# Rat_Social_Box_Extension.net
KiCad netlist of a schematic drawn in Altium Designer
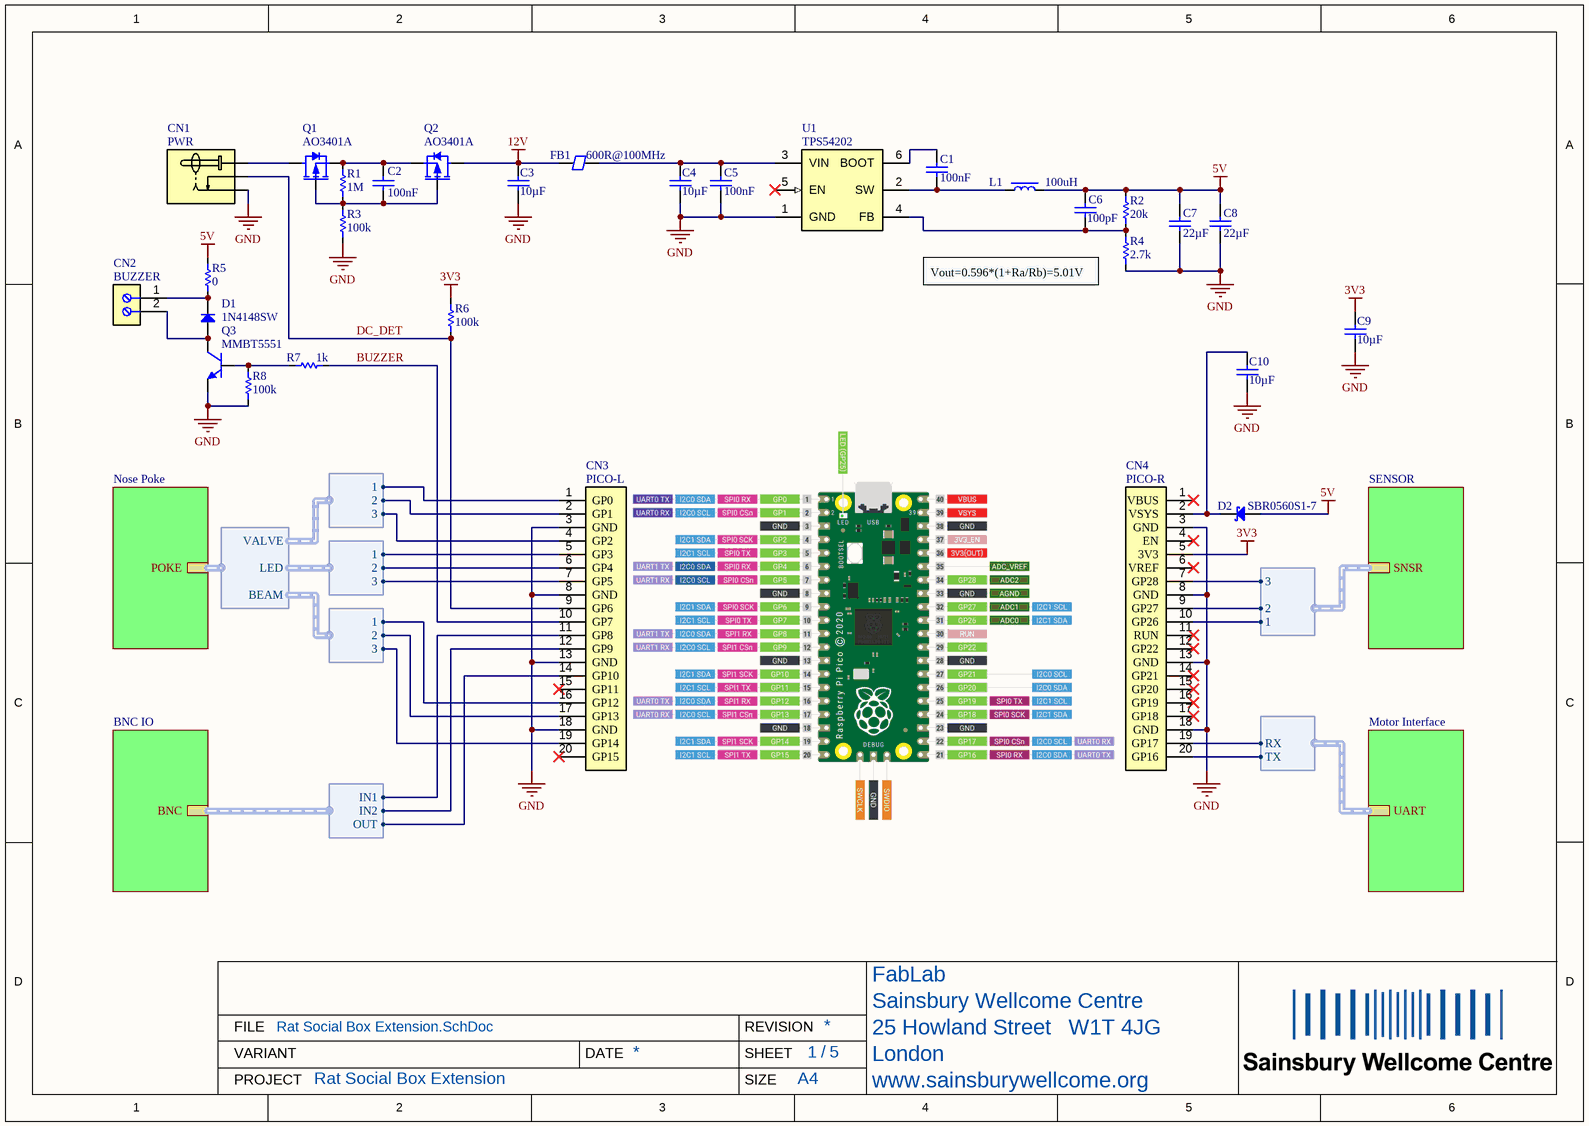
[diagram p0: Rat Social Box Extension.SchDoc]

(export (version "E")
  (design (tool "Eeschema 10.0.6"))
  (components
    (comp (ref "C1")
      (value "100nF")
      (footprint "CAP_CHIP_0603")
      (description "0603 Multilayer Ceramic Capacitors MLCC")
      (fields (field (name "TOLERANCE") "10%") (field (name "PARTNUMBER") "CC0603KRX7R9BB104"))
      (libsource (lib "Sainsbury Wellcome Centre") (part "Cap"))
    )
    (comp (ref "C2")
      (value "100nF")
      (footprint "CAP_CHIP_0603")
      (description "0603 Multilayer Ceramic Capacitors MLCC")
      (fields (field (name "PARTNUMBER") "CC0603KRX7R9BB104") (field (name "TOLERANCE") "10%"))
      (libsource (lib "Sainsbury Wellcome Centre") (part "Cap"))
    )
    (comp (ref "C3")
      (value "10µF")
      (footprint "CAP_CHIP_0603")
      (description "0603 Multilayer Ceramic Capacitors MLCC")
      (fields (field (name "PARTNUMBER") "CL10A106MA8NRNC") (field (name "TOLERANCE") "20%"))
      (libsource (lib "Sainsbury Wellcome Centre") (part "Cap"))
    )
    (comp (ref "C4")
      (value "10µF")
      (footprint "CAP_CHIP_0603")
      (description "0603 Multilayer Ceramic Capacitors MLCC")
      (fields (field (name "PARTNUMBER") "CL10A106MA8NRNC") (field (name "TOLERANCE") "20%"))
      (libsource (lib "Sainsbury Wellcome Centre") (part "Cap"))
    )
    (comp (ref "C5")
      (value "100nF")
      (footprint "CAP_CHIP_0603")
      (description "0603 Multilayer Ceramic Capacitors MLCC")
      (fields (field (name "TOLERANCE") "10%") (field (name "PARTNUMBER") "CC0603KRX7R9BB104"))
      (libsource (lib "Sainsbury Wellcome Centre") (part "Cap"))
    )
    (comp (ref "C6")
      (value "100pF")
      (footprint "CAP_CHIP_0603")
      (description "0603 Multilayer Ceramic Capacitors MLCC")
      (fields (field (name "TOLERANCE") "5%") (field (name "PARTNUMBER") "CL10C101JB8NNNC"))
      (libsource (lib "Sainsbury Wellcome Centre") (part "Cap"))
    )
    (comp (ref "C7")
      (value "22µF")
      (footprint "CAP_CHIP_0603")
      (description "0603 Multilayer Ceramic Capacitors MLCC")
      (fields (field (name "PARTNUMBER") "CL10A226MQ8NRNC") (field (name "TOLERANCE") "20%"))
      (libsource (lib "Sainsbury Wellcome Centre") (part "Cap"))
    )
    (comp (ref "C8")
      (value "22µF")
      (footprint "CAP_CHIP_0603")
      (description "0603 Multilayer Ceramic Capacitors MLCC")
      (fields (field (name "PARTNUMBER") "CL10A226MQ8NRNC") (field (name "TOLERANCE") "20%"))
      (libsource (lib "Sainsbury Wellcome Centre") (part "Cap"))
    )
    (comp (ref "C9")
      (value "10µF")
      (footprint "CAP_CHIP_0603")
      (description "0603 Multilayer Ceramic Capacitors MLCC")
      (fields (field (name "PARTNUMBER") "CL10A106MA8NRNC") (field (name "TOLERANCE") "20%"))
      (libsource (lib "Sainsbury Wellcome Centre") (part "Cap"))
    )
    (comp (ref "C10")
      (value "10µF")
      (footprint "CAP_CHIP_0603")
      (description "0603 Multilayer Ceramic Capacitors MLCC")
      (fields (field (name "PARTNUMBER") "CL10A106MA8NRNC") (field (name "TOLERANCE") "20%"))
      (libsource (lib "Sainsbury Wellcome Centre") (part "Cap"))
    )
    (comp (ref "CN1")
      (value "PWR")
      (footprint "DC-005-2.0")
      (description "Surface Mount, Right Angle 2.5A 24V SMD DC Power Connector")
      (fields (field (name "PARTNUMBER") "DC-005-2.5A-2.0-SMT"))
      (libsource (lib "Sainsbury Wellcome Centre") (part "DC Power Jack"))
    )
    (comp (ref "CN2")
      (value "BUZZER")
      (footprint "TH-5.00-1X2P")
      (description "1x2P 20A -40℃~+105℃ 250V Green 12~22 Direct Insert 5mm 2.5 1 2 Plugin,P=5mm Screw Terminal Blocks")
      (fields (field (name "PARTNUMBER") "WJ128V-5.0-2P"))
      (libsource (lib "Sainsbury Wellcome Centre") (part "Terminal Block 2"))
    )
    (comp (ref "CN3")
      (value "PICO-L")
      (footprint "FM_2.54_1X20P")
      (description "8.5mm Square Hole TH,P=2.54mm Female Headers")
      (fields (field (name "PARTNUMBER") "22850120ANG1SYA01"))
      (libsource (lib "Sainsbury Wellcome Centre") (part "Header_1X20P"))
    )
    (comp (ref "CN4")
      (value "PICO-R")
      (footprint "FM_2.54_1X20P")
      (description "8.5mm Square Hole TH,P=2.54mm Female Headers")
      (fields (field (name "PARTNUMBER") "22850120ANG1SYA01"))
      (libsource (lib "") (part "Header_1X20P_1"))
    )
    (comp (ref "D1")
      (value "1N4148SW")
      (footprint "SOD323")
      (description "100V Single 1.25V@150mA 4ns 150mA SOD-323 Switching Diode")
      (libsource (lib "Sainsbury Wellcome Centre") (part "Diode 2P"))
    )
    (comp (ref "D2")
      (value "SBR0560S1-7")
      (footprint "SOD123")
      (description "Diode Schottky 60V 0.5A 2-Pin SOD-123 T/R")
      (libsource (lib "Sainsbury Wellcome Centre") (part "Diode-Schottky"))
    )
    (comp (ref "FB1")
      (value "600R@100MHz")
      (footprint "FB_CHIP_0805")
      (description "Ferrite Chip, 1 Function(s), 0.5A, 2 Pin(s)")
      (fields (field (name "PARTNUMBER") "GZ2012D601TF") (field (name "Comment") "FB0805-600R-0.5A"))
      (libsource (lib "Sainsbury Wellcome Centre") (part "Bead"))
    )
    (comp (ref "L1")
      (value "100uH")
      (footprint "IND_PWR_0402L")
      (description "Inductor Power Shielded Wirewound 100uH 20% 100KHz Ferrite 450mA DCR 1515 Blister T/R")
      (fields (field (name "PARTNUMBER") "VLCF4020T-101MR26") (field (name "TOLERANCE") "20%"))
      (libsource (lib "Sainsbury Wellcome Centre") (part "Inductor"))
    )
    (comp (ref "Q1")
      (value "AO3401A")
      (footprint "SOT23")
      (description "30V 4A 44mΩ@10V,4.3A 1.4W 1.3V@250uA 1 PChannel SOT-23-3L MOSFETs")
      (fields (field (name "PARTNUMBER") "AO3401A"))
      (libsource (lib "Sainsbury Wellcome Centre") (part "PMOS"))
    )
    (comp (ref "Q2")
      (value "AO3401A")
      (footprint "SOT23")
      (description "30V 4A 44mΩ@10V,4.3A 1.4W 1.3V@250uA 1 PChannel SOT-23-3L MOSFETs")
      (fields (field (name "PARTNUMBER") "AO3401A"))
      (libsource (lib "Sainsbury Wellcome Centre") (part "PMOS"))
    )
    (comp (ref "Q3")
      (value "MMBT5551")
      (footprint "SOT23")
      (description "160V 300mW 200@10mA 5V 600mA NPN SOT-23 Bipolar Transistor")
      (fields (field (name "PARTNUMBER") "MMBT5551"))
      (libsource (lib "Sainsbury Wellcome Centre") (part "BJT NPN"))
    )
    (comp (ref "R1")
      (value "1M")
      (footprint "RES_CHIP_0603")
      (description "100mW Thick Film Resistors 75V ±100ppm/℃ ±1% 0603 Chip Resistor")
      (fields (field (name "PARTNUMBER") "0603WAF1004T5E") (field (name "TOLERANCE") "1%"))
      (libsource (lib "Sainsbury Wellcome Centre") (part "Res"))
    )
    (comp (ref "R2")
      (value "20k")
      (footprint "RES_CHIP_0603")
      (description "100mW Thick Film Resistors 75V ±100ppm/℃ ±1% 0603 Chip Resistor")
      (fields (field (name "TOLERANCE") "1%") (field (name "PARTNUMBER") "0603WAF2002T5E"))
      (libsource (lib "Sainsbury Wellcome Centre") (part "Res"))
    )
    (comp (ref "R3")
      (value "100k")
      (footprint "RES_CHIP_0603")
      (description "100mW Thick Film Resistors 75V ±100ppm/℃ ±1% 0603 Chip Resistor")
      (fields (field (name "PARTNUMBER") "0603WAF1003T5E") (field (name "TOLERANCE") "1%"))
      (libsource (lib "Sainsbury Wellcome Centre") (part "Res"))
    )
    (comp (ref "R4")
      (value "2.7k")
      (footprint "RES_CHIP_0603")
      (description "100mW Thick Film Resistors 75V ±100ppm/℃ ±1% 0603 Chip Resistor")
      (fields (field (name "TOLERANCE") "1%") (field (name "PARTNUMBER") "0603WAF2701T5E"))
      (libsource (lib "Sainsbury Wellcome Centre") (part "Res"))
    )
    (comp (ref "R5")
      (value "0")
      (footprint "RES_CHIP_1206")
      (description "250mW Thick Film Resistors 200V ±800ppm/℃ ±1% 0Ω 1206 Chip Resistor")
      (fields (field (name "TOLERANCE") "1%") (field (name "PARTNUMBER") "1206W4F0000T5E"))
      (libsource (lib "Sainsbury Wellcome Centre") (part "Res"))
    )
    (comp (ref "R6")
      (value "100k")
      (footprint "RES_CHIP_0603")
      (description "100mW Thick Film Resistors 75V ±100ppm/℃ ±1% 0603 Chip Resistor")
      (fields (field (name "PARTNUMBER") "0603WAF1003T5E") (field (name "TOLERANCE") "1%"))
      (libsource (lib "Sainsbury Wellcome Centre") (part "Res"))
    )
    (comp (ref "R7")
      (value "1k")
      (footprint "RES_CHIP_0603")
      (description "100mW Thick Film Resistors 75V ±100ppm/℃ ±1% 0603 Chip Resistor")
      (fields (field (name "PARTNUMBER") "0603WAF1001T5E") (field (name "TOLERANCE") "1%"))
      (libsource (lib "Sainsbury Wellcome Centre") (part "Res"))
    )
    (comp (ref "R8")
      (value "100k")
      (footprint "RES_CHIP_0603")
      (description "100mW Thick Film Resistors 75V ±100ppm/℃ ±1% 0603 Chip Resistor")
      (fields (field (name "PARTNUMBER") "0603WAF1003T5E") (field (name "TOLERANCE") "1%"))
      (libsource (lib "Sainsbury Wellcome Centre") (part "Res"))
    )
    (comp (ref "U1")
      (value "TPS54202")
      (footprint "SOT23-6")
      (description "Switching Regulator, Current-mode, 2A, 500kHz Switching Freq-Max, PDSO6")
      (fields (field (name "PARTNUMBER") "TPS54202DDCR"))
      (libsource (lib "Sainsbury Wellcome Centre") (part "TPS54202"))
    )
  )
  (nets
    (net (code "7") (name "/BUZZER") (class "Default")
      (node (ref "CN3") (pin "10") (pinfunction "GP7_10") (pintype "passive"))
      (node (ref "R7") (pin "2") (pinfunction "2_2") (pintype "passive"))
    )
    (net (code "8") (name "/DC_DET") (class "Default")
      (node (ref "CN1") (pin "3") (pinfunction "Detect_3") (pintype "passive"))
      (node (ref "CN3") (pin "9") (pinfunction "GP6_9") (pintype "passive"))
      (node (ref "R6") (pin "1") (pinfunction "1_1") (pintype "passive"))
    )
    (net (code "9") (name "/IN1") (class "Default")
      (node (ref "CN3") (pin "11") (pinfunction "GP8_11") (pintype "passive"))
    )
    (net (code "10") (name "/IN2") (class "Default")
      (node (ref "CN3") (pin "12") (pinfunction "GP9_12") (pintype "passive"))
    )
    (net (code "11") (name "/OUT") (class "Default")
      (node (ref "CN3") (pin "14") (pinfunction "GP10_14") (pintype "passive"))
    )
    (net (code "13") (name "/RX") (class "Default")
      (node (ref "CN4") (pin "19") (pinfunction "GP17_19") (pintype "passive"))
    )
    (net (code "14") (name "/TX") (class "Default")
      (node (ref "CN4") (pin "20") (pinfunction "GP16_20") (pintype "passive"))
    )
    (net (code "21") (name "3V3") (class "Default")
      (node (ref "C9") (pin "2") (pinfunction "2_2") (pintype "passive"))
      (node (ref "CN4") (pin "5") (pinfunction "3V3_5") (pintype "passive"))
      (node (ref "R6") (pin "2") (pinfunction "2_2") (pintype "passive"))
    )
    (net (code "22") (name "5V") (class "Default")
      (node (ref "C6") (pin "2") (pinfunction "2_2") (pintype "passive"))
      (node (ref "C7") (pin "2") (pinfunction "2_2") (pintype "passive"))
      (node (ref "C8") (pin "2") (pinfunction "2_2") (pintype "passive"))
      (node (ref "D2") (pin "2") (pinfunction "A_2") (pintype "passive"))
      (node (ref "L1") (pin "2") (pinfunction "2_2") (pintype "passive"))
      (node (ref "R2") (pin "2") (pinfunction "2_2") (pintype "passive"))
      (node (ref "R5") (pin "2") (pinfunction "2_2") (pintype "passive"))
    )
    (net (code "23") (name "12V") (class "Default")
      (node (ref "C3") (pin "2") (pinfunction "2_2") (pintype "passive"))
      (node (ref "FB1") (pin "1") (pinfunction "1_1") (pintype "passive"))
      (node (ref "Q2") (pin "3") (pinfunction "D_3") (pintype "passive"))
    )
    (net (code "24") (name "GND") (class "Default")
      (node (ref "C10") (pin "1") (pinfunction "1_1") (pintype "passive"))
      (node (ref "C3") (pin "1") (pinfunction "1_1") (pintype "passive"))
      (node (ref "C4") (pin "1") (pinfunction "1_1") (pintype "passive"))
      (node (ref "C5") (pin "1") (pinfunction "1_1") (pintype "passive"))
      (node (ref "C7") (pin "1") (pinfunction "1_1") (pintype "passive"))
      (node (ref "C8") (pin "1") (pinfunction "1_1") (pintype "passive"))
      (node (ref "C9") (pin "1") (pinfunction "1_1") (pintype "passive"))
      (node (ref "CN1") (pin "2") (pinfunction "Ring_2") (pintype "passive"))
      (node (ref "CN3") (pin "13") (pinfunction "GND_13") (pintype "passive"))
      (node (ref "CN3") (pin "18") (pinfunction "GND_18") (pintype "passive"))
      (node (ref "CN3") (pin "3") (pinfunction "GND_3") (pintype "passive"))
      (node (ref "CN3") (pin "8") (pinfunction "GND_8") (pintype "passive"))
      (node (ref "CN4") (pin "13") (pinfunction "GND_13") (pintype "passive"))
      (node (ref "CN4") (pin "18") (pinfunction "GND_18") (pintype "passive"))
      (node (ref "CN4") (pin "3") (pinfunction "GND_3") (pintype "passive"))
      (node (ref "CN4") (pin "8") (pinfunction "GND_8") (pintype "passive"))
      (node (ref "Q3") (pin "2") (pinfunction "E_2") (pintype "passive"))
      (node (ref "R3") (pin "1") (pinfunction "1_1") (pintype "passive"))
      (node (ref "R4") (pin "1") (pinfunction "1_1") (pintype "passive"))
      (node (ref "R8") (pin "1") (pinfunction "1_1") (pintype "passive"))
      (node (ref "U1") (pin "1") (pinfunction "GND_1") (pintype "power_in"))
    )
    (net (code "25") (name "Net-(CN1-Center)") (class "Default")
      (node (ref "CN1") (pin "1") (pinfunction "Center_1") (pintype "passive"))
      (node (ref "Q1") (pin "3") (pinfunction "D_3") (pintype "passive"))
    )
    (net (code "26") (name "Net-(CN4-VSYS)") (class "Default")
      (node (ref "C10") (pin "2") (pinfunction "2_2") (pintype "passive"))
      (node (ref "CN4") (pin "2") (pinfunction "VSYS_2") (pintype "passive"))
      (node (ref "D2") (pin "1") (pinfunction "C_1") (pintype "passive"))
    )
    (net (code "27") (name "Net-(D1-A)") (class "Default")
      (node (ref "CN2") (pin "2") (pinfunction "2_2") (pintype "passive"))
      (node (ref "D1") (pin "2") (pinfunction "A_2") (pintype "passive"))
      (node (ref "Q3") (pin "3") (pinfunction "C_3") (pintype "passive"))
    )
    (net (code "28") (name "Net-(D1-K)") (class "Default")
      (node (ref "CN2") (pin "1") (pinfunction "1_1") (pintype "passive"))
      (node (ref "D1") (pin "1") (pinfunction "K_1") (pintype "passive"))
      (node (ref "R5") (pin "1") (pinfunction "1_1") (pintype "passive"))
    )
    (net (code "29") (name "Net-(Q1-G)") (class "Default")
      (node (ref "C2") (pin "1") (pinfunction "1_1") (pintype "passive"))
      (node (ref "Q1") (pin "1") (pinfunction "G_1") (pintype "passive"))
      (node (ref "Q2") (pin "1") (pinfunction "G_1") (pintype "passive"))
      (node (ref "R1") (pin "1") (pinfunction "1_1") (pintype "passive"))
      (node (ref "R3") (pin "2") (pinfunction "2_2") (pintype "passive"))
    )
    (net (code "30") (name "Net-(Q1-S)") (class "Default")
      (node (ref "C2") (pin "2") (pinfunction "2_2") (pintype "passive"))
      (node (ref "Q1") (pin "2") (pinfunction "S_2") (pintype "passive"))
      (node (ref "Q2") (pin "2") (pinfunction "S_2") (pintype "passive"))
      (node (ref "R1") (pin "2") (pinfunction "2_2") (pintype "passive"))
    )
    (net (code "31") (name "Net-(Q3-B)") (class "Default")
      (node (ref "Q3") (pin "1") (pinfunction "B_1") (pintype "passive"))
      (node (ref "R7") (pin "1") (pinfunction "1_1") (pintype "passive"))
      (node (ref "R8") (pin "2") (pinfunction "2_2") (pintype "passive"))
    )
    (net (code "32") (name "Net-(U1-BOOT)") (class "Default")
      (node (ref "C1") (pin "2") (pinfunction "2_2") (pintype "passive"))
      (node (ref "U1") (pin "6") (pinfunction "BOOT_6") (pintype "passive"))
    )
    (net (code "33") (name "Net-(U1-FB)") (class "Default")
      (node (ref "C6") (pin "1") (pinfunction "1_1") (pintype "passive"))
      (node (ref "R2") (pin "1") (pinfunction "1_1") (pintype "passive"))
      (node (ref "R4") (pin "2") (pinfunction "2_2") (pintype "passive"))
      (node (ref "U1") (pin "4") (pinfunction "FB_4") (pintype "passive"))
    )
    (net (code "34") (name "Net-(U1-SW)") (class "Default")
      (node (ref "C1") (pin "1") (pinfunction "1_1") (pintype "passive"))
      (node (ref "L1") (pin "1") (pinfunction "1_1") (pintype "passive"))
      (node (ref "U1") (pin "2") (pinfunction "SW_2") (pintype "passive"))
    )
    (net (code "35") (name "Net-(U1-VIN)") (class "Default")
      (node (ref "C4") (pin "2") (pinfunction "2_2") (pintype "passive"))
      (node (ref "C5") (pin "2") (pinfunction "2_2") (pintype "passive"))
      (node (ref "FB1") (pin "2") (pinfunction "2_2") (pintype "passive"))
      (node (ref "U1") (pin "3") (pinfunction "VIN_3") (pintype "power_in"))
    )
    (net (code "36") (name "unconnected-(CN3-GP0-Pad1)") (class "Default")
      (node (ref "CN3") (pin "1") (pinfunction "GP0_1") (pintype "passive"))
    )
    (net (code "37") (name "unconnected-(CN3-GP1-Pad2)") (class "Default")
      (node (ref "CN3") (pin "2") (pinfunction "GP1_2") (pintype "passive"))
    )
    (net (code "38") (name "unconnected-(CN3-GP2-Pad4)") (class "Default")
      (node (ref "CN3") (pin "4") (pinfunction "GP2_4") (pintype "passive"))
    )
    (net (code "39") (name "unconnected-(CN3-GP3-Pad5)") (class "Default")
      (node (ref "CN3") (pin "5") (pinfunction "GP3_5") (pintype "passive"))
    )
    (net (code "40") (name "unconnected-(CN3-GP4-Pad6)") (class "Default")
      (node (ref "CN3") (pin "6") (pinfunction "GP4_6") (pintype "passive"))
    )
    (net (code "41") (name "unconnected-(CN3-GP5-Pad7)") (class "Default")
      (node (ref "CN3") (pin "7") (pinfunction "GP5_7") (pintype "passive"))
    )
    (net (code "42") (name "unconnected-(CN3-GP11-Pad15)") (class "Default")
      (node (ref "CN3") (pin "15") (pinfunction "GP11_15") (pintype "passive+no_connect"))
    )
    (net (code "43") (name "unconnected-(CN3-GP12-Pad16)") (class "Default")
      (node (ref "CN3") (pin "16") (pinfunction "GP12_16") (pintype "passive"))
    )
    (net (code "44") (name "unconnected-(CN3-GP13-Pad17)") (class "Default")
      (node (ref "CN3") (pin "17") (pinfunction "GP13_17") (pintype "passive"))
    )
    (net (code "45") (name "unconnected-(CN3-GP14-Pad19)") (class "Default")
      (node (ref "CN3") (pin "19") (pinfunction "GP14_19") (pintype "passive"))
    )
    (net (code "46") (name "unconnected-(CN3-GP15-Pad20)") (class "Default")
      (node (ref "CN3") (pin "20") (pinfunction "GP15_20") (pintype "passive+no_connect"))
    )
    (net (code "47") (name "unconnected-(CN4-EN-Pad4)") (class "Default")
      (node (ref "CN4") (pin "4") (pinfunction "EN_4") (pintype "passive+no_connect"))
    )
    (net (code "48") (name "unconnected-(CN4-GP18-Pad17)") (class "Default")
      (node (ref "CN4") (pin "17") (pinfunction "GP18_17") (pintype "passive+no_connect"))
    )
    (net (code "49") (name "unconnected-(CN4-GP19-Pad16)") (class "Default")
      (node (ref "CN4") (pin "16") (pinfunction "GP19_16") (pintype "passive+no_connect"))
    )
    (net (code "50") (name "unconnected-(CN4-GP20-Pad15)") (class "Default")
      (node (ref "CN4") (pin "15") (pinfunction "GP20_15") (pintype "passive+no_connect"))
    )
    (net (code "51") (name "unconnected-(CN4-GP21-Pad14)") (class "Default")
      (node (ref "CN4") (pin "14") (pinfunction "GP21_14") (pintype "passive+no_connect"))
    )
    (net (code "52") (name "unconnected-(CN4-GP22-Pad12)") (class "Default")
      (node (ref "CN4") (pin "12") (pinfunction "GP22_12") (pintype "passive+no_connect"))
    )
    (net (code "53") (name "unconnected-(CN4-GP26-Pad10)") (class "Default")
      (node (ref "CN4") (pin "10") (pinfunction "GP26_10") (pintype "passive"))
    )
    (net (code "54") (name "unconnected-(CN4-GP27-Pad9)") (class "Default")
      (node (ref "CN4") (pin "9") (pinfunction "GP27_9") (pintype "passive"))
    )
    (net (code "55") (name "unconnected-(CN4-GP28-Pad7)") (class "Default")
      (node (ref "CN4") (pin "7") (pinfunction "GP28_7") (pintype "passive"))
    )
    (net (code "56") (name "unconnected-(CN4-RUN-Pad11)") (class "Default")
      (node (ref "CN4") (pin "11") (pinfunction "RUN_11") (pintype "passive+no_connect"))
    )
    (net (code "57") (name "unconnected-(CN4-VBUS-Pad1)") (class "Default")
      (node (ref "CN4") (pin "1") (pinfunction "VBUS_1") (pintype "passive+no_connect"))
    )
    (net (code "58") (name "unconnected-(CN4-VREF-Pad6)") (class "Default")
      (node (ref "CN4") (pin "6") (pinfunction "VREF_6") (pintype "passive+no_connect"))
    )
    (net (code "59") (name "unconnected-(U1-EN-Pad5)") (class "Default")
      (node (ref "U1") (pin "5") (pinfunction "EN_5") (pintype "input+no_connect"))
    )
  )
)
